# Divider.net
KiCad netlist of a schematic drawn in Altium Designer
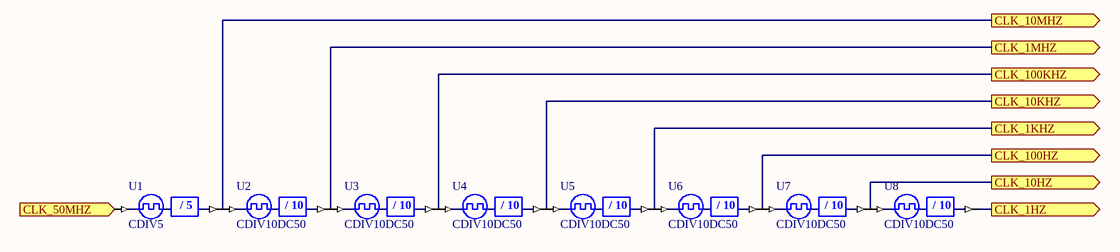
[diagram p0: Divider.schdoc]

(export (version "E")
  (design (tool "Eeschema 10.0.6"))
  (components
    (comp (ref "U1")
      (value "CDIV5")
      (description "Clock Divider by 5")
      (fields (field (name "PUBLISHER") "Altium Limited"))
      (libsource (lib "FPGA Generic") (part "CDIV5"))
    )
    (comp (ref "U2")
      (value "CDIV10DC50")
      (description "Clock Divider by 10 with 50% Duty Cycle Output")
      (fields (field (name "PUBLISHER") "Altium Limited"))
      (libsource (lib "FPGA Generic") (part "CDIV10DC50"))
    )
    (comp (ref "U3")
      (value "CDIV10DC50")
      (description "Clock Divider by 10 with 50% Duty Cycle Output")
      (fields (field (name "PUBLISHER") "Altium Limited"))
      (libsource (lib "FPGA Generic") (part "CDIV10DC50"))
    )
    (comp (ref "U4")
      (value "CDIV10DC50")
      (description "Clock Divider by 10 with 50% Duty Cycle Output")
      (fields (field (name "PUBLISHER") "Altium Limited"))
      (libsource (lib "FPGA Generic") (part "CDIV10DC50"))
    )
    (comp (ref "U5")
      (value "CDIV10DC50")
      (description "Clock Divider by 10 with 50% Duty Cycle Output")
      (fields (field (name "PUBLISHER") "Altium Limited"))
      (libsource (lib "FPGA Generic") (part "CDIV10DC50"))
    )
    (comp (ref "U6")
      (value "CDIV10DC50")
      (description "Clock Divider by 10 with 50% Duty Cycle Output")
      (fields (field (name "PUBLISHER") "Altium Limited"))
      (libsource (lib "FPGA Generic") (part "CDIV10DC50"))
    )
    (comp (ref "U7")
      (value "CDIV10DC50")
      (description "Clock Divider by 10 with 50% Duty Cycle Output")
      (fields (field (name "PUBLISHER") "Altium Limited"))
      (libsource (lib "FPGA Generic") (part "CDIV10DC50"))
    )
    (comp (ref "U8")
      (value "CDIV10DC50")
      (description "Clock Divider by 10 with 50% Duty Cycle Output")
      (fields (field (name "PUBLISHER") "Altium Limited"))
      (libsource (lib "FPGA Generic") (part "CDIV10DC50"))
    )
  )
  (nets
    (net (code "1") (name "/CLK_1HZ") (class "Default")
      (node (ref "U8") (pin "CLKDV") (pinfunction "CLKDV_CLKDV") (pintype "output"))
    )
    (net (code "2") (name "/CLK_1KHZ") (class "Default")
      (node (ref "U5") (pin "CLKDV") (pinfunction "CLKDV_CLKDV") (pintype "output"))
      (node (ref "U6") (pin "CLKIN") (pinfunction "CLKIN_CLKIN") (pintype "input"))
    )
    (net (code "3") (name "/CLK_1MHZ") (class "Default")
      (node (ref "U2") (pin "CLKDV") (pinfunction "CLKDV_CLKDV") (pintype "output"))
      (node (ref "U3") (pin "CLKIN") (pinfunction "CLKIN_CLKIN") (pintype "input"))
    )
    (net (code "4") (name "/CLK_10HZ") (class "Default")
      (node (ref "U7") (pin "CLKDV") (pinfunction "CLKDV_CLKDV") (pintype "output"))
      (node (ref "U8") (pin "CLKIN") (pinfunction "CLKIN_CLKIN") (pintype "input"))
    )
    (net (code "5") (name "/CLK_10KHZ") (class "Default")
      (node (ref "U4") (pin "CLKDV") (pinfunction "CLKDV_CLKDV") (pintype "output"))
      (node (ref "U5") (pin "CLKIN") (pinfunction "CLKIN_CLKIN") (pintype "input"))
    )
    (net (code "6") (name "/CLK_10MHZ") (class "Default")
      (node (ref "U1") (pin "CLKDV") (pinfunction "CLKDV_CLKDV") (pintype "output"))
      (node (ref "U2") (pin "CLKIN") (pinfunction "CLKIN_CLKIN") (pintype "input"))
    )
    (net (code "7") (name "/CLK_50MHZ") (class "Default")
      (node (ref "U1") (pin "CLKIN") (pinfunction "CLKIN_CLKIN") (pintype "input"))
    )
    (net (code "8") (name "/CLK_100HZ") (class "Default")
      (node (ref "U6") (pin "CLKDV") (pinfunction "CLKDV_CLKDV") (pintype "output"))
      (node (ref "U7") (pin "CLKIN") (pinfunction "CLKIN_CLKIN") (pintype "input"))
    )
    (net (code "9") (name "/CLK_100KHZ") (class "Default")
      (node (ref "U3") (pin "CLKDV") (pinfunction "CLKDV_CLKDV") (pintype "output"))
      (node (ref "U4") (pin "CLKIN") (pinfunction "CLKIN_CLKIN") (pintype "input"))
    )
  )
)
